# keyboard.net
KiCad netlist of a schematic drawn in Altium Designer
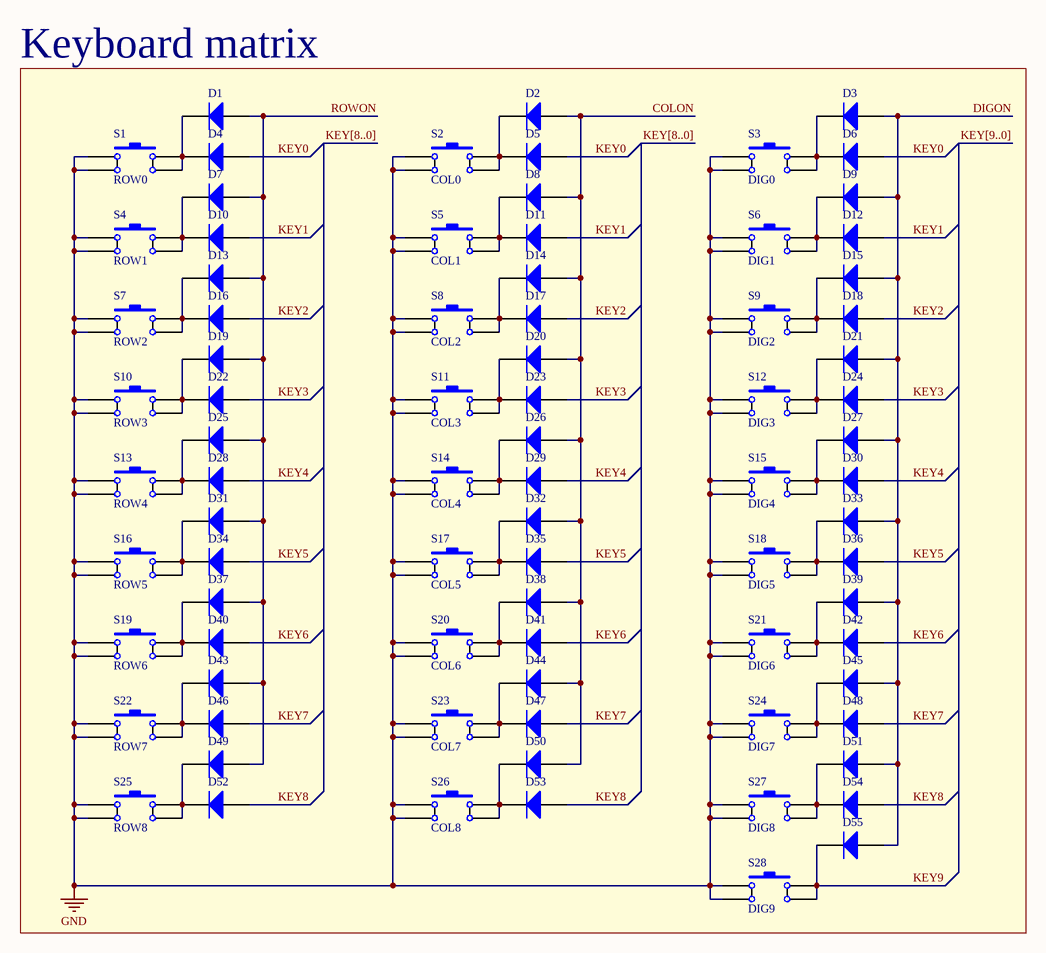
[diagram p0: keyboard.SchDoc]

(export (version "E")
  (design (tool "Eeschema 10.0.6"))
  (components
    (comp (ref "D1")
      (value "Diode 1N4007")
      (footprint "DIODE_SMC")
      (description "1 Amp General Purpose Rectifier")
      (fields (field (name "PUBLISHER") "Altium Limited"))
      (libsource (lib "Miscellaneous Devices") (part "Diode 1N4007"))
    )
    (comp (ref "D2")
      (value "Diode 1N4007")
      (footprint "DIODE_SMC")
      (description "1 Amp General Purpose Rectifier")
      (fields (field (name "PUBLISHER") "Altium Limited"))
      (libsource (lib "Miscellaneous Devices") (part "Diode 1N4007"))
    )
    (comp (ref "D3")
      (value "Diode 1N4007")
      (footprint "DIODE_SMC")
      (description "1 Amp General Purpose Rectifier")
      (fields (field (name "PUBLISHER") "Altium Limited"))
      (libsource (lib "Miscellaneous Devices") (part "Diode 1N4007"))
    )
    (comp (ref "D4")
      (value "Diode 1N4007")
      (footprint "DIODE_SMC")
      (description "1 Amp General Purpose Rectifier")
      (fields (field (name "PUBLISHER") "Altium Limited"))
      (libsource (lib "Miscellaneous Devices") (part "Diode 1N4007"))
    )
    (comp (ref "D5")
      (value "Diode 1N4007")
      (footprint "DIODE_SMC")
      (description "1 Amp General Purpose Rectifier")
      (fields (field (name "PUBLISHER") "Altium Limited"))
      (libsource (lib "Miscellaneous Devices") (part "Diode 1N4007"))
    )
    (comp (ref "D6")
      (value "Diode 1N4007")
      (footprint "DIODE_SMC")
      (description "1 Amp General Purpose Rectifier")
      (fields (field (name "PUBLISHER") "Altium Limited"))
      (libsource (lib "Miscellaneous Devices") (part "Diode 1N4007"))
    )
    (comp (ref "D7")
      (value "Diode 1N4007")
      (footprint "DIODE_SMC")
      (description "1 Amp General Purpose Rectifier")
      (fields (field (name "PUBLISHER") "Altium Limited"))
      (libsource (lib "Miscellaneous Devices") (part "Diode 1N4007"))
    )
    (comp (ref "D8")
      (value "Diode 1N4007")
      (footprint "DIODE_SMC")
      (description "1 Amp General Purpose Rectifier")
      (fields (field (name "PUBLISHER") "Altium Limited"))
      (libsource (lib "Miscellaneous Devices") (part "Diode 1N4007"))
    )
    (comp (ref "D9")
      (value "Diode 1N4007")
      (footprint "DIODE_SMC")
      (description "1 Amp General Purpose Rectifier")
      (fields (field (name "PUBLISHER") "Altium Limited"))
      (libsource (lib "Miscellaneous Devices") (part "Diode 1N4007"))
    )
    (comp (ref "D10")
      (value "Diode 1N4007")
      (footprint "DIODE_SMC")
      (description "1 Amp General Purpose Rectifier")
      (fields (field (name "PUBLISHER") "Altium Limited"))
      (libsource (lib "Miscellaneous Devices") (part "Diode 1N4007"))
    )
    (comp (ref "D11")
      (value "Diode 1N4007")
      (footprint "DIODE_SMC")
      (description "1 Amp General Purpose Rectifier")
      (fields (field (name "PUBLISHER") "Altium Limited"))
      (libsource (lib "Miscellaneous Devices") (part "Diode 1N4007"))
    )
    (comp (ref "D12")
      (value "Diode 1N4007")
      (footprint "DIODE_SMC")
      (description "1 Amp General Purpose Rectifier")
      (fields (field (name "PUBLISHER") "Altium Limited"))
      (libsource (lib "Miscellaneous Devices") (part "Diode 1N4007"))
    )
    (comp (ref "D13")
      (value "Diode 1N4007")
      (footprint "DIODE_SMC")
      (description "1 Amp General Purpose Rectifier")
      (fields (field (name "PUBLISHER") "Altium Limited"))
      (libsource (lib "Miscellaneous Devices") (part "Diode 1N4007"))
    )
    (comp (ref "D14")
      (value "Diode 1N4007")
      (footprint "DIODE_SMC")
      (description "1 Amp General Purpose Rectifier")
      (fields (field (name "PUBLISHER") "Altium Limited"))
      (libsource (lib "Miscellaneous Devices") (part "Diode 1N4007"))
    )
    (comp (ref "D15")
      (value "Diode 1N4007")
      (footprint "DIODE_SMC")
      (description "1 Amp General Purpose Rectifier")
      (fields (field (name "PUBLISHER") "Altium Limited"))
      (libsource (lib "Miscellaneous Devices") (part "Diode 1N4007"))
    )
    (comp (ref "D16")
      (value "Diode 1N4007")
      (footprint "DIODE_SMC")
      (description "1 Amp General Purpose Rectifier")
      (fields (field (name "PUBLISHER") "Altium Limited"))
      (libsource (lib "Miscellaneous Devices") (part "Diode 1N4007"))
    )
    (comp (ref "D17")
      (value "Diode 1N4007")
      (footprint "DIODE_SMC")
      (description "1 Amp General Purpose Rectifier")
      (fields (field (name "PUBLISHER") "Altium Limited"))
      (libsource (lib "Miscellaneous Devices") (part "Diode 1N4007"))
    )
    (comp (ref "D18")
      (value "Diode 1N4007")
      (footprint "DIODE_SMC")
      (description "1 Amp General Purpose Rectifier")
      (fields (field (name "PUBLISHER") "Altium Limited"))
      (libsource (lib "Miscellaneous Devices") (part "Diode 1N4007"))
    )
    (comp (ref "D19")
      (value "Diode 1N4007")
      (footprint "DIODE_SMC")
      (description "1 Amp General Purpose Rectifier")
      (fields (field (name "PUBLISHER") "Altium Limited"))
      (libsource (lib "Miscellaneous Devices") (part "Diode 1N4007"))
    )
    (comp (ref "D20")
      (value "Diode 1N4007")
      (footprint "DIODE_SMC")
      (description "1 Amp General Purpose Rectifier")
      (fields (field (name "PUBLISHER") "Altium Limited"))
      (libsource (lib "Miscellaneous Devices") (part "Diode 1N4007"))
    )
    (comp (ref "D21")
      (value "Diode 1N4007")
      (footprint "DIODE_SMC")
      (description "1 Amp General Purpose Rectifier")
      (fields (field (name "PUBLISHER") "Altium Limited"))
      (libsource (lib "Miscellaneous Devices") (part "Diode 1N4007"))
    )
    (comp (ref "D22")
      (value "Diode 1N4007")
      (footprint "DIODE_SMC")
      (description "1 Amp General Purpose Rectifier")
      (fields (field (name "PUBLISHER") "Altium Limited"))
      (libsource (lib "Miscellaneous Devices") (part "Diode 1N4007"))
    )
    (comp (ref "D23")
      (value "Diode 1N4007")
      (footprint "DIODE_SMC")
      (description "1 Amp General Purpose Rectifier")
      (fields (field (name "PUBLISHER") "Altium Limited"))
      (libsource (lib "Miscellaneous Devices") (part "Diode 1N4007"))
    )
    (comp (ref "D24")
      (value "Diode 1N4007")
      (footprint "DIODE_SMC")
      (description "1 Amp General Purpose Rectifier")
      (fields (field (name "PUBLISHER") "Altium Limited"))
      (libsource (lib "Miscellaneous Devices") (part "Diode 1N4007"))
    )
    (comp (ref "D25")
      (value "Diode 1N4007")
      (footprint "DIODE_SMC")
      (description "1 Amp General Purpose Rectifier")
      (fields (field (name "PUBLISHER") "Altium Limited"))
      (libsource (lib "Miscellaneous Devices") (part "Diode 1N4007"))
    )
    (comp (ref "D26")
      (value "Diode 1N4007")
      (footprint "DIODE_SMC")
      (description "1 Amp General Purpose Rectifier")
      (fields (field (name "PUBLISHER") "Altium Limited"))
      (libsource (lib "Miscellaneous Devices") (part "Diode 1N4007"))
    )
    (comp (ref "D27")
      (value "Diode 1N4007")
      (footprint "DIODE_SMC")
      (description "1 Amp General Purpose Rectifier")
      (fields (field (name "PUBLISHER") "Altium Limited"))
      (libsource (lib "Miscellaneous Devices") (part "Diode 1N4007"))
    )
    (comp (ref "D28")
      (value "Diode 1N4007")
      (footprint "DIODE_SMC")
      (description "1 Amp General Purpose Rectifier")
      (fields (field (name "PUBLISHER") "Altium Limited"))
      (libsource (lib "Miscellaneous Devices") (part "Diode 1N4007"))
    )
    (comp (ref "D29")
      (value "Diode 1N4007")
      (footprint "DIODE_SMC")
      (description "1 Amp General Purpose Rectifier")
      (fields (field (name "PUBLISHER") "Altium Limited"))
      (libsource (lib "Miscellaneous Devices") (part "Diode 1N4007"))
    )
    (comp (ref "D30")
      (value "Diode 1N4007")
      (footprint "DIODE_SMC")
      (description "1 Amp General Purpose Rectifier")
      (fields (field (name "PUBLISHER") "Altium Limited"))
      (libsource (lib "Miscellaneous Devices") (part "Diode 1N4007"))
    )
    (comp (ref "D31")
      (value "Diode 1N4007")
      (footprint "DIODE_SMC")
      (description "1 Amp General Purpose Rectifier")
      (fields (field (name "PUBLISHER") "Altium Limited"))
      (libsource (lib "Miscellaneous Devices") (part "Diode 1N4007"))
    )
    (comp (ref "D32")
      (value "Diode 1N4007")
      (footprint "DIODE_SMC")
      (description "1 Amp General Purpose Rectifier")
      (fields (field (name "PUBLISHER") "Altium Limited"))
      (libsource (lib "Miscellaneous Devices") (part "Diode 1N4007"))
    )
    (comp (ref "D33")
      (value "Diode 1N4007")
      (footprint "DIODE_SMC")
      (description "1 Amp General Purpose Rectifier")
      (fields (field (name "PUBLISHER") "Altium Limited"))
      (libsource (lib "Miscellaneous Devices") (part "Diode 1N4007"))
    )
    (comp (ref "D34")
      (value "Diode 1N4007")
      (footprint "DIODE_SMC")
      (description "1 Amp General Purpose Rectifier")
      (fields (field (name "PUBLISHER") "Altium Limited"))
      (libsource (lib "Miscellaneous Devices") (part "Diode 1N4007"))
    )
    (comp (ref "D35")
      (value "Diode 1N4007")
      (footprint "DIODE_SMC")
      (description "1 Amp General Purpose Rectifier")
      (fields (field (name "PUBLISHER") "Altium Limited"))
      (libsource (lib "Miscellaneous Devices") (part "Diode 1N4007"))
    )
    (comp (ref "D36")
      (value "Diode 1N4007")
      (footprint "DIODE_SMC")
      (description "1 Amp General Purpose Rectifier")
      (fields (field (name "PUBLISHER") "Altium Limited"))
      (libsource (lib "Miscellaneous Devices") (part "Diode 1N4007"))
    )
    (comp (ref "D37")
      (value "Diode 1N4007")
      (footprint "DIODE_SMC")
      (description "1 Amp General Purpose Rectifier")
      (fields (field (name "PUBLISHER") "Altium Limited"))
      (libsource (lib "Miscellaneous Devices") (part "Diode 1N4007"))
    )
    (comp (ref "D38")
      (value "Diode 1N4007")
      (footprint "DIODE_SMC")
      (description "1 Amp General Purpose Rectifier")
      (fields (field (name "PUBLISHER") "Altium Limited"))
      (libsource (lib "Miscellaneous Devices") (part "Diode 1N4007"))
    )
    (comp (ref "D39")
      (value "Diode 1N4007")
      (footprint "DIODE_SMC")
      (description "1 Amp General Purpose Rectifier")
      (fields (field (name "PUBLISHER") "Altium Limited"))
      (libsource (lib "Miscellaneous Devices") (part "Diode 1N4007"))
    )
    (comp (ref "D40")
      (value "Diode 1N4007")
      (footprint "DIODE_SMC")
      (description "1 Amp General Purpose Rectifier")
      (fields (field (name "PUBLISHER") "Altium Limited"))
      (libsource (lib "Miscellaneous Devices") (part "Diode 1N4007"))
    )
    (comp (ref "D41")
      (value "Diode 1N4007")
      (footprint "DIODE_SMC")
      (description "1 Amp General Purpose Rectifier")
      (fields (field (name "PUBLISHER") "Altium Limited"))
      (libsource (lib "Miscellaneous Devices") (part "Diode 1N4007"))
    )
    (comp (ref "D42")
      (value "Diode 1N4007")
      (footprint "DIODE_SMC")
      (description "1 Amp General Purpose Rectifier")
      (fields (field (name "PUBLISHER") "Altium Limited"))
      (libsource (lib "Miscellaneous Devices") (part "Diode 1N4007"))
    )
    (comp (ref "D43")
      (value "Diode 1N4007")
      (footprint "DIODE_SMC")
      (description "1 Amp General Purpose Rectifier")
      (fields (field (name "PUBLISHER") "Altium Limited"))
      (libsource (lib "Miscellaneous Devices") (part "Diode 1N4007"))
    )
    (comp (ref "D44")
      (value "Diode 1N4007")
      (footprint "DIODE_SMC")
      (description "1 Amp General Purpose Rectifier")
      (fields (field (name "PUBLISHER") "Altium Limited"))
      (libsource (lib "Miscellaneous Devices") (part "Diode 1N4007"))
    )
    (comp (ref "D45")
      (value "Diode 1N4007")
      (footprint "DIODE_SMC")
      (description "1 Amp General Purpose Rectifier")
      (fields (field (name "PUBLISHER") "Altium Limited"))
      (libsource (lib "Miscellaneous Devices") (part "Diode 1N4007"))
    )
    (comp (ref "D46")
      (value "Diode 1N4007")
      (footprint "DIODE_SMC")
      (description "1 Amp General Purpose Rectifier")
      (fields (field (name "PUBLISHER") "Altium Limited"))
      (libsource (lib "Miscellaneous Devices") (part "Diode 1N4007"))
    )
    (comp (ref "D47")
      (value "Diode 1N4007")
      (footprint "DIODE_SMC")
      (description "1 Amp General Purpose Rectifier")
      (fields (field (name "PUBLISHER") "Altium Limited"))
      (libsource (lib "Miscellaneous Devices") (part "Diode 1N4007"))
    )
    (comp (ref "D48")
      (value "Diode 1N4007")
      (footprint "DIODE_SMC")
      (description "1 Amp General Purpose Rectifier")
      (fields (field (name "PUBLISHER") "Altium Limited"))
      (libsource (lib "Miscellaneous Devices") (part "Diode 1N4007"))
    )
    (comp (ref "D49")
      (value "Diode 1N4007")
      (footprint "DIODE_SMC")
      (description "1 Amp General Purpose Rectifier")
      (fields (field (name "PUBLISHER") "Altium Limited"))
      (libsource (lib "Miscellaneous Devices") (part "Diode 1N4007"))
    )
    (comp (ref "D50")
      (value "Diode 1N4007")
      (footprint "DIODE_SMC")
      (description "1 Amp General Purpose Rectifier")
      (fields (field (name "PUBLISHER") "Altium Limited"))
      (libsource (lib "Miscellaneous Devices") (part "Diode 1N4007"))
    )
    (comp (ref "D51")
      (value "Diode 1N4007")
      (footprint "DIODE_SMC")
      (description "1 Amp General Purpose Rectifier")
      (fields (field (name "PUBLISHER") "Altium Limited"))
      (libsource (lib "Miscellaneous Devices") (part "Diode 1N4007"))
    )
    (comp (ref "D52")
      (value "Diode 1N4007")
      (footprint "DIODE_SMC")
      (description "1 Amp General Purpose Rectifier")
      (fields (field (name "PUBLISHER") "Altium Limited"))
      (libsource (lib "Miscellaneous Devices") (part "Diode 1N4007"))
    )
    (comp (ref "D53")
      (value "Diode 1N4007")
      (footprint "DIODE_SMC")
      (description "1 Amp General Purpose Rectifier")
      (fields (field (name "PUBLISHER") "Altium Limited"))
      (libsource (lib "Miscellaneous Devices") (part "Diode 1N4007"))
    )
    (comp (ref "D54")
      (value "Diode 1N4007")
      (footprint "DIODE_SMC")
      (description "1 Amp General Purpose Rectifier")
      (fields (field (name "PUBLISHER") "Altium Limited"))
      (libsource (lib "Miscellaneous Devices") (part "Diode 1N4007"))
    )
    (comp (ref "D55")
      (value "Diode 1N4007")
      (footprint "DIODE_SMC")
      (description "1 Amp General Purpose Rectifier")
      (fields (field (name "PUBLISHER") "Altium Limited"))
      (libsource (lib "Miscellaneous Devices") (part "Diode 1N4007"))
    )
    (comp (ref "S1")
      (value "ROW0")
      (footprint "SW_1825910-6-4")
      (description "Switch")
      (fields (field (name "PUBLISHER") "Altium Limited"))
      (libsource (lib "tactile_button") (part "SW-PB"))
    )
    (comp (ref "S2")
      (value "COL0")
      (footprint "SW_1825910-6-4")
      (description "Switch")
      (fields (field (name "PUBLISHER") "Altium Limited"))
      (libsource (lib "tactile_button") (part "SW-PB"))
    )
    (comp (ref "S3")
      (value "DIG0")
      (footprint "SW_1825910-6-4")
      (description "Switch")
      (fields (field (name "PUBLISHER") "Altium Limited"))
      (libsource (lib "tactile_button") (part "SW-PB"))
    )
    (comp (ref "S4")
      (value "ROW1")
      (footprint "SW_1825910-6-4")
      (description "Switch")
      (fields (field (name "PUBLISHER") "Altium Limited"))
      (libsource (lib "tactile_button") (part "SW-PB"))
    )
    (comp (ref "S5")
      (value "COL1")
      (footprint "SW_1825910-6-4")
      (description "Switch")
      (fields (field (name "PUBLISHER") "Altium Limited"))
      (libsource (lib "tactile_button") (part "SW-PB"))
    )
    (comp (ref "S6")
      (value "DIG1")
      (footprint "SW_1825910-6-4")
      (description "Switch")
      (fields (field (name "PUBLISHER") "Altium Limited"))
      (libsource (lib "tactile_button") (part "SW-PB"))
    )
    (comp (ref "S7")
      (value "ROW2")
      (footprint "SW_1825910-6-4")
      (description "Switch")
      (fields (field (name "PUBLISHER") "Altium Limited"))
      (libsource (lib "tactile_button") (part "SW-PB"))
    )
    (comp (ref "S8")
      (value "COL2")
      (footprint "SW_1825910-6-4")
      (description "Switch")
      (fields (field (name "PUBLISHER") "Altium Limited"))
      (libsource (lib "tactile_button") (part "SW-PB"))
    )
    (comp (ref "S9")
      (value "DIG2")
      (footprint "SW_1825910-6-4")
      (description "Switch")
      (fields (field (name "PUBLISHER") "Altium Limited"))
      (libsource (lib "tactile_button") (part "SW-PB"))
    )
    (comp (ref "S10")
      (value "ROW3")
      (footprint "SW_1825910-6-4")
      (description "Switch")
      (fields (field (name "PUBLISHER") "Altium Limited"))
      (libsource (lib "tactile_button") (part "SW-PB"))
    )
    (comp (ref "S11")
      (value "COL3")
      (footprint "SW_1825910-6-4")
      (description "Switch")
      (fields (field (name "PUBLISHER") "Altium Limited"))
      (libsource (lib "tactile_button") (part "SW-PB"))
    )
    (comp (ref "S12")
      (value "DIG3")
      (footprint "SW_1825910-6-4")
      (description "Switch")
      (fields (field (name "PUBLISHER") "Altium Limited"))
      (libsource (lib "tactile_button") (part "SW-PB"))
    )
    (comp (ref "S13")
      (value "ROW4")
      (footprint "SW_1825910-6-4")
      (description "Switch")
      (fields (field (name "PUBLISHER") "Altium Limited"))
      (libsource (lib "tactile_button") (part "SW-PB"))
    )
    (comp (ref "S14")
      (value "COL4")
      (footprint "SW_1825910-6-4")
      (description "Switch")
      (fields (field (name "PUBLISHER") "Altium Limited"))
      (libsource (lib "tactile_button") (part "SW-PB"))
    )
    (comp (ref "S15")
      (value "DIG4")
      (footprint "SW_1825910-6-4")
      (description "Switch")
      (fields (field (name "PUBLISHER") "Altium Limited"))
      (libsource (lib "tactile_button") (part "SW-PB"))
    )
    (comp (ref "S16")
      (value "ROW5")
      (footprint "SW_1825910-6-4")
      (description "Switch")
      (fields (field (name "PUBLISHER") "Altium Limited"))
      (libsource (lib "tactile_button") (part "SW-PB"))
    )
    (comp (ref "S17")
      (value "COL5")
      (footprint "SW_1825910-6-4")
      (description "Switch")
      (fields (field (name "PUBLISHER") "Altium Limited"))
      (libsource (lib "tactile_button") (part "SW-PB"))
    )
    (comp (ref "S18")
      (value "DIG5")
      (footprint "SW_1825910-6-4")
      (description "Switch")
      (fields (field (name "PUBLISHER") "Altium Limited"))
      (libsource (lib "tactile_button") (part "SW-PB"))
    )
    (comp (ref "S19")
      (value "ROW6")
      (footprint "SW_1825910-6-4")
      (description "Switch")
      (fields (field (name "PUBLISHER") "Altium Limited"))
      (libsource (lib "tactile_button") (part "SW-PB"))
    )
    (comp (ref "S20")
      (value "COL6")
      (footprint "SW_1825910-6-4")
      (description "Switch")
      (fields (field (name "PUBLISHER") "Altium Limited"))
      (libsource (lib "tactile_button") (part "SW-PB"))
    )
    (comp (ref "S21")
      (value "DIG6")
      (footprint "SW_1825910-6-4")
      (description "Switch")
      (fields (field (name "PUBLISHER") "Altium Limited"))
      (libsource (lib "tactile_button") (part "SW-PB"))
    )
    (comp (ref "S22")
      (value "ROW7")
      (footprint "SW_1825910-6-4")
      (description "Switch")
      (fields (field (name "PUBLISHER") "Altium Limited"))
      (libsource (lib "tactile_button") (part "SW-PB"))
    )
    (comp (ref "S23")
      (value "COL7")
      (footprint "SW_1825910-6-4")
      (description "Switch")
      (fields (field (name "PUBLISHER") "Altium Limited"))
      (libsource (lib "tactile_button") (part "SW-PB"))
    )
    (comp (ref "S24")
      (value "DIG7")
      (footprint "SW_1825910-6-4")
      (description "Switch")
      (fields (field (name "PUBLISHER") "Altium Limited"))
      (libsource (lib "tactile_button") (part "SW-PB"))
    )
    (comp (ref "S25")
      (value "ROW8")
      (footprint "SW_1825910-6-4")
      (description "Switch")
      (fields (field (name "PUBLISHER") "Altium Limited"))
      (libsource (lib "tactile_button") (part "SW-PB"))
    )
    (comp (ref "S26")
      (value "COL8")
      (footprint "SW_1825910-6-4")
      (description "Switch")
      (fields (field (name "PUBLISHER") "Altium Limited"))
      (libsource (lib "tactile_button") (part "SW-PB"))
    )
    (comp (ref "S27")
      (value "DIG8")
      (footprint "SW_1825910-6-4")
      (description "Switch")
      (fields (field (name "PUBLISHER") "Altium Limited"))
      (libsource (lib "tactile_button") (part "SW-PB"))
    )
    (comp (ref "S28")
      (value "DIG9")
      (footprint "SW_1825910-6-4")
      (description "Switch")
      (fields (field (name "PUBLISHER") "Altium Limited"))
      (libsource (lib "tactile_button") (part "SW-PB"))
    )
  )
  (nets
    (net (code "1") (name "/COLON") (class "Default")
      (node (ref "D14") (pin "1") (pinfunction "A_1") (pintype "passive"))
      (node (ref "D2") (pin "1") (pinfunction "A_1") (pintype "passive"))
      (node (ref "D20") (pin "1") (pinfunction "A_1") (pintype "passive"))
      (node (ref "D26") (pin "1") (pinfunction "A_1") (pintype "passive"))
      (node (ref "D32") (pin "1") (pinfunction "A_1") (pintype "passive"))
      (node (ref "D38") (pin "1") (pinfunction "A_1") (pintype "passive"))
      (node (ref "D44") (pin "1") (pinfunction "A_1") (pintype "passive"))
      (node (ref "D50") (pin "1") (pinfunction "A_1") (pintype "passive"))
      (node (ref "D8") (pin "1") (pinfunction "A_1") (pintype "passive"))
    )
    (net (code "2") (name "/DIGON") (class "Default")
      (node (ref "D15") (pin "1") (pinfunction "A_1") (pintype "passive"))
      (node (ref "D21") (pin "1") (pinfunction "A_1") (pintype "passive"))
      (node (ref "D27") (pin "1") (pinfunction "A_1") (pintype "passive"))
      (node (ref "D3") (pin "1") (pinfunction "A_1") (pintype "passive"))
      (node (ref "D33") (pin "1") (pinfunction "A_1") (pintype "passive"))
      (node (ref "D39") (pin "1") (pinfunction "A_1") (pintype "passive"))
      (node (ref "D45") (pin "1") (pinfunction "A_1") (pintype "passive"))
      (node (ref "D51") (pin "1") (pinfunction "A_1") (pintype "passive"))
      (node (ref "D55") (pin "1") (pinfunction "A_1") (pintype "passive"))
      (node (ref "D9") (pin "1") (pinfunction "A_1") (pintype "passive"))
    )
    (net (code "3") (name "/KEY0") (class "Default")
      (node (ref "D4") (pin "1") (pinfunction "A_1") (pintype "passive"))
      (node (ref "D5") (pin "1") (pinfunction "A_1") (pintype "passive"))
      (node (ref "D6") (pin "1") (pinfunction "A_1") (pintype "passive"))
    )
    (net (code "4") (name "/KEY1") (class "Default")
      (node (ref "D10") (pin "1") (pinfunction "A_1") (pintype "passive"))
      (node (ref "D11") (pin "1") (pinfunction "A_1") (pintype "passive"))
      (node (ref "D12") (pin "1") (pinfunction "A_1") (pintype "passive"))
    )
    (net (code "5") (name "/KEY2") (class "Default")
      (node (ref "D16") (pin "1") (pinfunction "A_1") (pintype "passive"))
      (node (ref "D17") (pin "1") (pinfunction "A_1") (pintype "passive"))
      (node (ref "D18") (pin "1") (pinfunction "A_1") (pintype "passive"))
    )
    (net (code "6") (name "/KEY3") (class "Default")
      (node (ref "D22") (pin "1") (pinfunction "A_1") (pintype "passive"))
      (node (ref "D23") (pin "1") (pinfunction "A_1") (pintype "passive"))
      (node (ref "D24") (pin "1") (pinfunction "A_1") (pintype "passive"))
    )
    (net (code "7") (name "/KEY4") (class "Default")
      (node (ref "D28") (pin "1") (pinfunction "A_1") (pintype "passive"))
      (node (ref "D29") (pin "1") (pinfunction "A_1") (pintype "passive"))
      (node (ref "D30") (pin "1") (pinfunction "A_1") (pintype "passive"))
    )
    (net (code "8") (name "/KEY5") (class "Default")
      (node (ref "D34") (pin "1") (pinfunction "A_1") (pintype "passive"))
      (node (ref "D35") (pin "1") (pinfunction "A_1") (pintype "passive"))
      (node (ref "D36") (pin "1") (pinfunction "A_1") (pintype "passive"))
    )
    (net (code "9") (name "/KEY6") (class "Default")
      (node (ref "D40") (pin "1") (pinfunction "A_1") (pintype "passive"))
      (node (ref "D41") (pin "1") (pinfunction "A_1") (pintype "passive"))
      (node (ref "D42") (pin "1") (pinfunction "A_1") (pintype "passive"))
    )
    (net (code "10") (name "/KEY7") (class "Default")
      (node (ref "D46") (pin "1") (pinfunction "A_1") (pintype "passive"))
      (node (ref "D47") (pin "1") (pinfunction "A_1") (pintype "passive"))
      (node (ref "D48") (pin "1") (pinfunction "A_1") (pintype "passive"))
    )
    (net (code "11") (name "/KEY8") (class "Default")
      (node (ref "D52") (pin "1") (pinfunction "A_1") (pintype "passive"))
      (node (ref "D53") (pin "1") (pinfunction "A_1") (pintype "passive"))
      (node (ref "D54") (pin "1") (pinfunction "A_1") (pintype "passive"))
    )
    (net (code "12") (name "/KEY9") (class "Default")
      (node (ref "D55") (pin "2") (pinfunction "K_2") (pintype "passive"))
      (node (ref "S28") (pin "1") (pinfunction "1_1") (pintype "passive"))
      (node (ref "S28") (pin "2") (pinfunction "2_2") (pintype "passive"))
    )
    (net (code "15") (name "/ROWON") (class "Default")
      (node (ref "D1") (pin "1") (pinfunction "A_1") (pintype "passive"))
      (node (ref "D13") (pin "1") (pinfunction "A_1") (pintype "passive"))
      (node (ref "D19") (pin "1") (pinfunction "A_1") (pintype "passive"))
      (node (ref "D25") (pin "1") (pinfunction "A_1") (pintype "passive"))
      (node (ref "D31") (pin "1") (pinfunction "A_1") (pintype "passive"))
      (node (ref "D37") (pin "1") (pinfunction "A_1") (pintype "passive"))
      (node (ref "D43") (pin "1") (pinfunction "A_1") (pintype "passive"))
      (node (ref "D49") (pin "1") (pinfunction "A_1") (pintype "passive"))
      (node (ref "D7") (pin "1") (pinfunction "A_1") (pintype "passive"))
    )
    (net (code "16") (name "GND") (class "Default")
      (node (ref "S1") (pin "3") (pinfunction "3_3") (pintype "passive"))
      (node (ref "S1") (pin "4") (pinfunction "4_4") (pintype "passive"))
      (node (ref "S10") (pin "3") (pinfunction "3_3") (pintype "passive"))
      (node (ref "S10") (pin "4") (pinfunction "4_4") (pintype "passive"))
      (node (ref "S11") (pin "3") (pinfunction "3_3") (pintype "passive"))
      (node (ref "S11") (pin "4") (pinfunction "4_4") (pintype "passive"))
      (node (ref "S12") (pin "3") (pinfunction "3_3") (pintype "passive"))
      (node (ref "S12") (pin "4") (pinfunction "4_4") (pintype "passive"))
      (node (ref "S13") (pin "3") (pinfunction "3_3") (pintype "passive"))
      (node (ref "S13") (pin "4") (pinfunction "4_4") (pintype "passive"))
      (node (ref "S14") (pin "3") (pinfunction "3_3") (pintype "passive"))
      (node (ref "S14") (pin "4") (pinfunction "4_4") (pintype "passive"))
      (node (ref "S15") (pin "3") (pinfunction "3_3") (pintype "passive"))
      (node (ref "S15") (pin "4") (pinfunction "4_4") (pintype "passive"))
      (node (ref "S16") (pin "3") (pinfunction "3_3") (pintype "passive"))
      (node (ref "S16") (pin "4") (pinfunction "4_4") (pintype "passive"))
      (node (ref "S17") (pin "3") (pinfunction "3_3") (pintype "passive"))
      (node (ref "S17") (pin "4") (pinfunction "4_4") (pintype "passive"))
      (node (ref "S18") (pin "3") (pinfunction "3_3") (pintype "passive"))
      (node (ref "S18") (pin "4") (pinfunction "4_4") (pintype "passive"))
      (node (ref "S19") (pin "3") (pinfunction "3_3") (pintype "passive"))
      (node (ref "S19") (pin "4") (pinfunction "4_4") (pintype "passive"))
      (node (ref "S2") (pin "3") (pinfunction "3_3") (pintype "passive"))
      (node (ref "S2") (pin "4") (pinfunction "4_4") (pintype "passive"))
      (node (ref "S20") (pin "3") (pinfunction "3_3") (pintype "passive"))
      (node (ref "S20") (pin "4") (pinfunction "4_4") (pintype "passive"))
      (node (ref "S21") (pin "3") (pinfunction "3_3") (pintype "passive"))
      (node (ref "S21") (pin "4") (pinfunction "4_4") (pintype "passive"))
      (node (ref "S22") (pin "3") (pinfunction "3_3") (pintype "passive"))
      (node (ref "S22") (pin "4") (pinfunction "4_4") (pintype "passive"))
      (node (ref "S23") (pin "3") (pinfunction "3_3") (pintype "passive"))
      (node (ref "S23") (pin "4") (pinfunction "4_4") (pintype "passive"))
      (node (ref "S24") (pin "3") (pinfunction "3_3") (pintype "passive"))
      (node (ref "S24") (pin "4") (pinfunction "4_4") (pintype "passive"))
      (node (ref "S25") (pin "3") (pinfunction "3_3") (pintype "passive"))
      (node (ref "S25") (pin "4") (pinfunction "4_4") (pintype "passive"))
      (node (ref "S26") (pin "3") (pinfunction "3_3") (pintype "passive"))
      (node (ref "S26") (pin "4") (pinfunction "4_4") (pintype "passive"))
      (node (ref "S27") (pin "3") (pinfunction "3_3") (pintype "passive"))
      (node (ref "S27") (pin "4") (pinfunction "4_4") (pintype "passive"))
      (node (ref "S28") (pin "3") (pinfunction "3_3") (pintype "passive"))
      (node (ref "S28") (pin "4") (pinfunction "4_4") (pintype "passive"))
      (node (ref "S3") (pin "3") (pinfunction "3_3") (pintype "passive"))
      (node (ref "S3") (pin "4") (pinfunction "4_4") (pintype "passive"))
      (node (ref "S4") (pin "3") (pinfunction "3_3") (pintype "passive"))
      (node (ref "S4") (pin "4") (pinfunction "4_4") (pintype "passive"))
      (node (ref "S5") (pin "3") (pinfunction "3_3") (pintype "passive"))
      (node (ref "S5") (pin "4") (pinfunction "4_4") (pintype "passive"))
      (node (ref "S6") (pin "3") (pinfunction "3_3") (pintype "passive"))
      (node (ref "S6") (pin "4") (pinfunction "4_4") (pintype "passive"))
      (node (ref "S7") (pin "3") (pinfunction "3_3") (pintype "passive"))
      (node (ref "S7") (pin "4") (pinfunction "4_4") (pintype "passive"))
      (node (ref "S8") (pin "3") (pinfunction "3_3") (pintype "passive"))
      (node (ref "S8") (pin "4") (pinfunction "4_4") (pintype "passive"))
      (node (ref "S9") (pin "3") (pinfunction "3_3") (pintype "passive"))
      (node (ref "S9") (pin "4") (pinfunction "4_4") (pintype "passive"))
    )
    (net (code "17") (name "Net-(D1-K)") (class "Default")
      (node (ref "D1") (pin "2") (pinfunction "K_2") (pintype "passive"))
      (node (ref "D4") (pin "2") (pinfunction "K_2") (pintype "passive"))
      (node (ref "S1") (pin "1") (pinfunction "1_1") (pintype "passive"))
      (node (ref "S1") (pin "2") (pinfunction "2_2") (pintype "passive"))
    )
    (net (code "18") (name "Net-(D2-K)") (class "Default")
      (node (ref "D2") (pin "2") (pinfunction "K_2") (pintype "passive"))
      (node (ref "D5") (pin "2") (pinfunction "K_2") (pintype "passive"))
      (node (ref "S2") (pin "1") (pinfunction "1_1") (pintype "passive"))
      (node (ref "S2") (pin "2") (pinfunction "2_2") (pintype "passive"))
    )
    (net (code "19") (name "Net-(D3-K)") (class "Default")
      (node (ref "D3") (pin "2") (pinfunction "K_2") (pintype "passive"))
      (node (ref "D6") (pin "2") (pinfunction "K_2") (pintype "passive"))
      (node (ref "S3") (pin "1") (pinfunction "1_1") (pintype "passive"))
      (node (ref "S3") (pin "2") (pinfunction "2_2") (pintype "passive"))
    )
    (net (code "20") (name "Net-(D10-K)") (class "Default")
      (node (ref "D10") (pin "2") (pinfunction "K_2") (pintype "passive"))
      (node (ref "D7") (pin "2") (pinfunction "K_2") (pintype "passive"))
      (node (ref "S4") (pin "1") (pinfunction "1_1") (pintype "passive"))
      (node (ref "S4") (pin "2") (pinfunction "2_2") (pintype "passive"))
    )
    (net (code "21") (name "Net-(D11-K)") (class "Default")
      (node (ref "D11") (pin "2") (pinfunction "K_2") (pintype "passive"))
      (node (ref "D8") (pin "2") (pinfunction "K_2") (pintype "passive"))
      (node (ref "S5") (pin "1") (pinfunction "1_1") (pintype "passive"))
      (node (ref "S5") (pin "2") (pinfunction "2_2") (pintype "passive"))
    )
    (net (code "22") (name "Net-(D12-K)") (class "Default")
      (node (ref "D12") (pin "2") (pinfunction "K_2") (pintype "passive"))
      (node (ref "D9") (pin "2") (pinfunction "K_2") (pintype "passive"))
      (node (ref "S6") (pin "1") (pinfunction "1_1") (pintype "passive"))
      (node (ref "S6") (pin "2") (pinfunction "2_2") (pintype "passive"))
    )
    (net (code "23") (name "Net-(D13-K)") (class "Default")
      (node (ref "D13") (pin "2") (pinfunction "K_2") (pintype "passive"))
      (node (ref "D16") (pin "2") (pinfunction "K_2") (pintype "passive"))
      (node (ref "S7") (pin "1") (pinfunction "1_1") (pintype "passive"))
      (node (ref "S7") (pin "2") (pinfunction "2_2") (pintype "passive"))
    )
    (net (code "24") (name "Net-(D14-K)") (class "Default")
      (node (ref "D14") (pin "2") (pinfunction "K_2") (pintype "passive"))
      (node (ref "D17") (pin "2") (pinfunction "K_2") (pintype "passive"))
      (node (ref "S8") (pin "1") (pinfunction "1_1") (pintype "passive"))
      (node (ref "S8") (pin "2") (pinfunction "2_2") (pintype "passive"))
    )
    (net (code "25") (name "Net-(D15-K)") (class "Default")
      (node (ref "D15") (pin "2") (pinfunction "K_2") (pintype "passive"))
      (node (ref "D18") (pin "2") (pinfunction "K_2") (pintype "passive"))
      (node (ref "S9") (pin "1") (pinfunction "1_1") (pintype "passive"))
      (node (ref "S9") (pin "2") (pinfunction "2_2") (pintype "passive"))
    )
    (net (code "26") (name "Net-(D19-K)") (class "Default")
      (node (ref "D19") (pin "2") (pinfunction "K_2") (pintype "passive"))
      (node (ref "D22") (pin "2") (pinfunction "K_2") (pintype "passive"))
      (node (ref "S10") (pin "1") (pinfunction "1_1") (pintype "passive"))
      (node (ref "S10") (pin "2") (pinfunction "2_2") (pintype "passive"))
    )
    (net (code "27") (name "Net-(D20-K)") (class "Default")
      (node (ref "D20") (pin "2") (pinfunction "K_2") (pintype "passive"))
      (node (ref "D23") (pin "2") (pinfunction "K_2") (pintype "passive"))
      (node (ref "S11") (pin "1") (pinfunction "1_1") (pintype "passive"))
      (node (ref "S11") (pin "2") (pinfunction "2_2") (pintype "passive"))
    )
    (net (code "28") (name "Net-(D21-K)") (class "Default")
      (node (ref "D21") (pin "2") (pinfunction "K_2") (pintype "passive"))
      (node (ref "D24") (pin "2") (pinfunction "K_2") (pintype "passive"))
      (node (ref "S12") (pin "1") (pinfunction "1_1") (pintype "passive"))
      (node (ref "S12") (pin "2") (pinfunction "2_2") (pintype "passive"))
    )
    (net (code "29") (name "Net-(D25-K)") (class "Default")
      (node (ref "D25") (pin "2") (pinfunction "K_2") (pintype "passive"))
      (node (ref "D28") (pin "2") (pinfunction "K_2") (pintype "passive"))
      (node (ref "S13") (pin "1") (pinfunction "1_1") (pintype "passive"))
      (node (ref "S13") (pin "2") (pinfunction "2_2") (pintype "passive"))
    )
    (net (code "30") (name "Net-(D26-K)") (class "Default")
      (node (ref "D26") (pin "2") (pinfunction "K_2") (pintype "passive"))
      (node (ref "D29") (pin "2") (pinfunction "K_2") (pintype "passive"))
      (node (ref "S14") (pin "1") (pinfunction "1_1") (pintype "passive"))
      (node (ref "S14") (pin "2") (pinfunction "2_2") (pintype "passive"))
    )
    (net (code "31") (name "Net-(D27-K)") (class "Default")
      (node (ref "D27") (pin "2") (pinfunction "K_2") (pintype "passive"))
      (node (ref "D30") (pin "2") (pinfunction "K_2") (pintype "passive"))
      (node (ref "S15") (pin "1") (pinfunction "1_1") (pintype "passive"))
      (node (ref "S15") (pin "2") (pinfunction "2_2") (pintype "passive"))
    )
    (net (code "32") (name "Net-(D31-K)") (class "Default")
      (node (ref "D31") (pin "2") (pinfunction "K_2") (pintype "passive"))
      (node (ref "D34") (pin "2") (pinfunction "K_2") (pintype "passive"))
      (node (ref "S16") (pin "1") (pinfunction "1_1") (pintype "passive"))
      (node (ref "S16") (pin "2") (pinfunction "2_2") (pintype "passive"))
    )
    (net (code "33") (name "Net-(D32-K)") (class "Default")
      (node (ref "D32") (pin "2") (pinfunction "K_2") (pintype "passive"))
      (node (ref "D35") (pin "2") (pinfunction "K_2") (pintype "passive"))
      (node (ref "S17") (pin "1") (pinfunction "1_1") (pintype "passive"))
      (node (ref "S17") (pin "2") (pinfunction "2_2") (pintype "passive"))
    )
    (net (code "34") (name "Net-(D33-K)") (class "Default")
      (node (ref "D33") (pin "2") (pinfunction "K_2") (pintype "passive"))
      (node (ref "D36") (pin "2") (pinfunction "K_2") (pintype "passive"))
      (node (ref "S18") (pin "1") (pinfunction "1_1") (pintype "passive"))
      (node (ref "S18") (pin "2") (pinfunction "2_2") (pintype "passive"))
    )
    (net (code "35") (name "Net-(D37-K)") (class "Default")
      (node (ref "D37") (pin "2") (pinfunction "K_2") (pintype "passive"))
      (node (ref "D40") (pin "2") (pinfunction "K_2") (pintype "passive"))
      (node (ref "S19") (pin "1") (pinfunction "1_1") (pintype "passive"))
      (node (ref "S19") (pin "2") (pinfunction "2_2") (pintype "passive"))
    )
    (net (code "36") (name "Net-(D38-K)") (class "Default")
      (node (ref "D38") (pin "2") (pinfunction "K_2") (pintype "passive"))
      (node (ref "D41") (pin "2") (pinfunction "K_2") (pintype "passive"))
      (node (ref "S20") (pin "1") (pinfunction "1_1") (pintype "passive"))
      (node (ref "S20") (pin "2") (pinfunction "2_2") (pintype "passive"))
    )
    (net (code "37") (name "Net-(D39-K)") (class "Default")
      (node (ref "D39") (pin "2") (pinfunction "K_2") (pintype "passive"))
      (node (ref "D42") (pin "2") (pinfunction "K_2") (pintype "passive"))
      (node (ref "S21") (pin "1") (pinfunction "1_1") (pintype "passive"))
      (node (ref "S21") (pin "2") (pinfunction "2_2") (pintype "passive"))
    )
    (net (code "38") (name "Net-(D43-K)") (class "Default")
      (node (ref "D43") (pin "2") (pinfunction "K_2") (pintype "passive"))
      (node (ref "D46") (pin "2") (pinfunction "K_2") (pintype "passive"))
      (node (ref "S22") (pin "1") (pinfunction "1_1") (pintype "passive"))
      (node (ref "S22") (pin "2") (pinfunction "2_2") (pintype "passive"))
    )
    (net (code "39") (name "Net-(D44-K)") (class "Default")
      (node (ref "D44") (pin "2") (pinfunction "K_2") (pintype "passive"))
      (node (ref "D47") (pin "2") (pinfunction "K_2") (pintype "passive"))
      (node (ref "S23") (pin "1") (pinfunction "1_1") (pintype "passive"))
      (node (ref "S23") (pin "2") (pinfunction "2_2") (pintype "passive"))
    )
    (net (code "40") (name "Net-(D45-K)") (class "Default")
      (node (ref "D45") (pin "2") (pinfunction "K_2") (pintype "passive"))
      (node (ref "D48") (pin "2") (pinfunction "K_2") (pintype "passive"))
      (node (ref "S24") (pin "1") (pinfunction "1_1") (pintype "passive"))
      (node (ref "S24") (pin "2") (pinfunction "2_2") (pintype "passive"))
    )
    (net (code "41") (name "Net-(D49-K)") (class "Default")
      (node (ref "D49") (pin "2") (pinfunction "K_2") (pintype "passive"))
      (node (ref "D52") (pin "2") (pinfunction "K_2") (pintype "passive"))
      (node (ref "S25") (pin "1") (pinfunction "1_1") (pintype "passive"))
      (node (ref "S25") (pin "2") (pinfunction "2_2") (pintype "passive"))
    )
    (net (code "42") (name "Net-(D50-K)") (class "Default")
      (node (ref "D50") (pin "2") (pinfunction "K_2") (pintype "passive"))
      (node (ref "D53") (pin "2") (pinfunction "K_2") (pintype "passive"))
      (node (ref "S26") (pin "1") (pinfunction "1_1") (pintype "passive"))
      (node (ref "S26") (pin "2") (pinfunction "2_2") (pintype "passive"))
    )
    (net (code "43") (name "Net-(D51-K)") (class "Default")
      (node (ref "D51") (pin "2") (pinfunction "K_2") (pintype "passive"))
      (node (ref "D54") (pin "2") (pinfunction "K_2") (pintype "passive"))
      (node (ref "S27") (pin "1") (pinfunction "1_1") (pintype "passive"))
      (node (ref "S27") (pin "2") (pinfunction "2_2") (pintype "passive"))
    )
  )
)
